# output.net
KiCad netlist of a schematic drawn in EAGLE
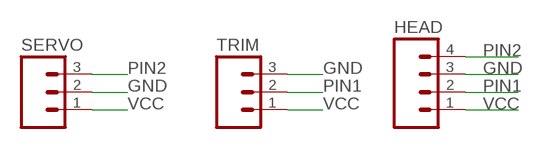
[diagram p0: schematic, sheet 1]

(export (version "E")
  (design (tool "Eeschema 10.0.6"))
  (components
    (comp (ref "HEAD")
      (value "M04LONGPADS")
      (footprint "eagle-import:1X04_LONGPADS")
      (libsource (lib "eagle-import") (part "M04LONGPADS"))
    )
    (comp (ref "SERVO")
      (value "M03PTH")
      (footprint "eagle-import:1X03")
      (libsource (lib "eagle-import") (part "M03PTH"))
    )
    (comp (ref "TRIM")
      (value "M03PTH")
      (footprint "eagle-import:1X03")
      (libsource (lib "eagle-import") (part "M03PTH"))
    )
  )
  (nets
    (net (code "1") (name "/GND") (class "Default")
      (node (ref "HEAD") (pin "3") (pinfunction "3_3") (pintype "passive"))
      (node (ref "SERVO") (pin "2") (pinfunction "2_2") (pintype "passive"))
      (node (ref "TRIM") (pin "3") (pinfunction "3_3") (pintype "passive"))
    )
    (net (code "2") (name "/PIN1") (class "Default")
      (node (ref "HEAD") (pin "2") (pinfunction "2_2") (pintype "passive"))
      (node (ref "TRIM") (pin "2") (pinfunction "2_2") (pintype "passive"))
    )
    (net (code "3") (name "/PIN2") (class "Default")
      (node (ref "HEAD") (pin "4") (pinfunction "4_4") (pintype "passive"))
      (node (ref "SERVO") (pin "3") (pinfunction "3_3") (pintype "passive"))
    )
    (net (code "4") (name "/VCC") (class "Default")
      (node (ref "HEAD") (pin "1") (pinfunction "1_1") (pintype "passive"))
      (node (ref "SERVO") (pin "1") (pinfunction "1_1") (pintype "passive"))
      (node (ref "TRIM") (pin "1") (pinfunction "1_1") (pintype "passive"))
    )
  )
)
